# molex_breakout.net
KiCad netlist of a schematic drawn in EAGLE
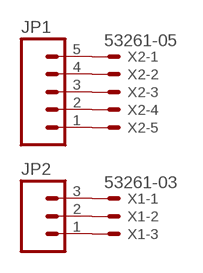
[diagram p0: schematic, sheet 1]

(export (version "E")
  (design (tool "Eeschema 10.0.6"))
  (components
    (comp (ref "JP1")
      (value "M05PTH")
      (footprint "eagle-import:1X05")
      (libsource (lib "eagle-import") (part "M05PTH"))
    )
    (comp (ref "JP2")
      (value "M03PTH")
      (footprint "eagle-import:1X03")
      (libsource (lib "eagle-import") (part "M03PTH"))
    )
    (comp (ref "X1")
      (value "53261-03")
      (footprint "eagle-import:53261-03")
      (fields (field (name "MF") "MOLEX") (field (name "MPN") "53261-0390"))
      (libsource (lib "eagle-import") (part "53?-03261"))
    )
    (comp (ref "X2")
      (value "53261-05")
      (footprint "eagle-import:53261-05")
      (libsource (lib "eagle-import") (part "53?-05261"))
    )
  )
  (nets
    (net (code "1") (name "Net-(X1A-S)") (class "Default")
      (node (ref "JP2") (pin "3") (pinfunction "3_3") (pintype "passive"))
      (node (ref "X1") (pin "1") (pinfunction "S_1") (pintype "passive"))
    )
    (net (code "2") (name "Net-(X1B-S)") (class "Default")
      (node (ref "JP2") (pin "2") (pinfunction "2_2") (pintype "passive"))
      (node (ref "X1") (pin "2") (pinfunction "S_2") (pintype "passive"))
    )
    (net (code "3") (name "Net-(X1C-S)") (class "Default")
      (node (ref "JP2") (pin "1") (pinfunction "1_1") (pintype "passive"))
      (node (ref "X1") (pin "3") (pinfunction "S_3") (pintype "passive"))
    )
    (net (code "4") (name "Net-(X2A-S)") (class "Default")
      (node (ref "JP1") (pin "5") (pinfunction "5_5") (pintype "passive"))
      (node (ref "X2") (pin "1") (pinfunction "S_1") (pintype "passive"))
    )
    (net (code "5") (name "Net-(X2B-S)") (class "Default")
      (node (ref "JP1") (pin "4") (pinfunction "4_4") (pintype "passive"))
      (node (ref "X2") (pin "2") (pinfunction "S_2") (pintype "passive"))
    )
    (net (code "6") (name "Net-(X2C-S)") (class "Default")
      (node (ref "JP1") (pin "3") (pinfunction "3_3") (pintype "passive"))
      (node (ref "X2") (pin "3") (pinfunction "S_3") (pintype "passive"))
    )
    (net (code "7") (name "Net-(X2D-S)") (class "Default")
      (node (ref "JP1") (pin "2") (pinfunction "2_2") (pintype "passive"))
      (node (ref "X2") (pin "4") (pinfunction "S_4") (pintype "passive"))
    )
    (net (code "8") (name "Net-(X2E-S)") (class "Default")
      (node (ref "JP1") (pin "1") (pinfunction "1_1") (pintype "passive"))
      (node (ref "X2") (pin "5") (pinfunction "S_5") (pintype "passive"))
    )
  )
)
